# Capstone_Motor_Driver.net
KiCad netlist of a schematic drawn in Altium Designer
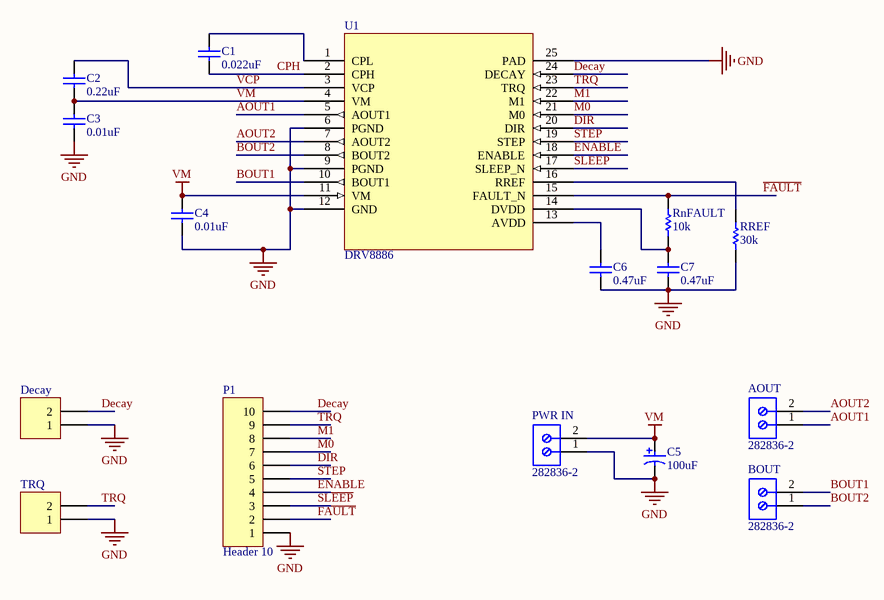
[diagram p0: Capstone_Motor_Driver.SchDoc]

(export (version "E")
  (design (tool "Eeschema 10.0.6"))
  (components
    (comp (ref "AOUT")
      (value "282836-2")
      (footprint "TECO-282836-2_V")
      (description "Female Header, Pitch 5 mm, 1 x 2 Position, Height 10 mm, Tail Length 3.5 mm, Rohs, Bulk")
      (fields (field (name "VOLTAGE") "300V") (field (name "MANUFACTURER") "TE Connectivity"))
      (libsource (lib "IFFF_DRV8886_Power_Breakout") (part "CMP-1684-00017-1"))
    )
    (comp (ref "BOUT")
      (value "282836-2")
      (footprint "TECO-282836-2_V")
      (description "Female Header, Pitch 5 mm, 1 x 2 Position, Height 10 mm, Tail Length 3.5 mm, Rohs, Bulk")
      (fields (field (name "VOLTAGE") "300V") (field (name "MANUFACTURER") "TE Connectivity"))
      (libsource (lib "IFFF_DRV8886_Power_Breakout") (part "CMP-1684-00017-1"))
    )
    (comp (ref "C1")
      (value "0.022uF")
      (footprint "CAPC2013X94X50ML20T25")
      (fields
        (field (name "MANUFACTURER") "AVX Interconnect / Elco")
        (field (name "PART NUMBER") "08055C223JAT2A")
      )
      (libsource (lib "Altium Content Vault") (part "CAP"))
    )
    (comp (ref "C2")
      (value "0.22uF")
      (footprint "CAPC2013X145X50NL20T25")
      (description "0805")
      (fields (field (name "PART NUMBER") "C0805C224K5RAC7800") (field (name "MANUFACTURER") "Kemet"))
      (libsource (lib "Altium Content Vault") (part "CAP"))
    )
    (comp (ref "C3")
      (value "0.01uF")
      (footprint "CAPC2013X88X50ML20T25")
      (description "0805")
      (fields (field (name "MANUFACTURER") "Kemet") (field (name "PART NUMBER") "C0805C103J5RACTU"))
      (libsource (lib "Altium Content Vault") (part "CAP"))
    )
    (comp (ref "C4")
      (value "0.01uF")
      (footprint "CAPC2013X88X50ML20T25")
      (description "0805")
      (fields (field (name "MANUFACTURER") "Kemet") (field (name "PART NUMBER") "C0805C103J5RACTU"))
      (libsource (lib "Altium Content Vault") (part "CAP"))
    )
    (comp (ref "C5")
      (value "100uF")
      (footprint "PNSC-FK-V-F_V")
      (fields (field (name "MANUFACTURER") "Panasonic"))
      (libsource (lib "Altium Content Vault") (part "CAP-P-2"))
    )
    (comp (ref "C6")
      (value "0.47uF")
      (footprint "CAPC2013X110X50NL20T25")
      (description "0805")
      (fields (field (name "MANUFACTURER") "Kemet") (field (name "PART NUMBER") "C0805C474K5RACTU"))
      (libsource (lib "Altium Content Vault") (part "CAP"))
    )
    (comp (ref "C7")
      (value "0.47uF")
      (footprint "CAPC2013X110X50NL20T25")
      (description "0805")
      (fields (field (name "MANUFACTURER") "Kemet") (field (name "PART NUMBER") "C0805C474K5RACTU"))
      (libsource (lib "Altium Content Vault") (part "CAP"))
    )
    (comp (ref "Decay")
      (value "Header 2")
      (footprint "HDR1X2")
      (description "Header, 2-Pin")
      (fields (field (name "PUBLISHER") "Altium Limited"))
      (libsource (lib "Miscellaneous Connectors") (part "Header 2"))
    )
    (comp (ref "P1")
      (value "Header 10")
      (footprint "HDR1X10")
      (description "Header, 10-Pin")
      (fields (field (name "PUBLISHER") "Altium Limited"))
      (libsource (lib "Miscellaneous Connectors") (part "Header 10"))
    )
    (comp (ref "PWR IN")
      (value "282836-2")
      (footprint "TECO-282836-2_V")
      (description "Female Header, Pitch 5 mm, 1 x 2 Position, Height 10 mm, Tail Length 3.5 mm, Rohs, Bulk")
      (fields (field (name "VOLTAGE") "300V") (field (name "MANUFACTURER") "TE Connectivity"))
      (libsource (lib "IFFF_DRV8886_Power_Breakout") (part "CMP-1684-00017-1"))
    )
    (comp (ref "RnFAULT")
      (value "10k")
      (footprint "RESC2013X60X40LL20T25_A")
      (fields (field (name "TOLERANCE") "0.1%") (field (name "MANUFACTURER") "Panasonic"))
      (libsource (lib "Altium Content Vault") (part "RES-2"))
    )
    (comp (ref "RREF")
      (value "30k")
      (footprint "RESC2013X60X40LL20T25_A")
      (fields (field (name "TOLERANCE") "0.1%") (field (name "MANUFACTURER") "Panasonic"))
      (libsource (lib "Altium Content Vault") (part "RES-2"))
    )
    (comp (ref "TRQ")
      (value "Header 2")
      (footprint "HDR1X2")
      (description "Header, 2-Pin")
      (fields (field (name "PUBLISHER") "Altium Limited"))
      (libsource (lib "Miscellaneous Connectors") (part "Header 2"))
    )
    (comp (ref "U1")
      (value "DRV8886")
      (footprint "PWP0024B_N")
      (libsource (lib "IFFF_DRV8886_Power_Breakout") (part "DRV8886"))
    )
  )
  (nets
    (net (code "1") (name "/AOUT1") (class "Default")
      (node (ref "AOUT") (pin "1") (pinfunction "1_1") (pintype "passive"))
      (node (ref "U1") (pin "5") (pinfunction "AOUT1_5") (pintype "output"))
    )
    (net (code "2") (name "/AOUT2") (class "Default")
      (node (ref "AOUT") (pin "2") (pinfunction "2_2") (pintype "passive"))
      (node (ref "U1") (pin "7") (pinfunction "AOUT2_7") (pintype "output"))
    )
    (net (code "3") (name "/BOUT1") (class "Default")
      (node (ref "BOUT") (pin "2") (pinfunction "2_2") (pintype "passive"))
      (node (ref "U1") (pin "10") (pinfunction "BOUT1_10") (pintype "output"))
    )
    (net (code "4") (name "/BOUT2") (class "Default")
      (node (ref "BOUT") (pin "1") (pinfunction "1_1") (pintype "passive"))
      (node (ref "U1") (pin "8") (pinfunction "BOUT2_8") (pintype "output"))
    )
    (net (code "5") (name "/CPH") (class "Default")
      (node (ref "C1") (pin "1") (pinfunction "1_1") (pintype "passive"))
      (node (ref "U1") (pin "2") (pinfunction "CPH_2") (pintype "passive"))
    )
    (net (code "6") (name "/DIR") (class "Default")
      (node (ref "P1") (pin "6") (pinfunction "6_6") (pintype "passive"))
      (node (ref "U1") (pin "20") (pinfunction "DIR_20") (pintype "input"))
    )
    (net (code "7") (name "/Decay") (class "Default")
      (node (ref "Decay") (pin "2") (pinfunction "2_2") (pintype "passive"))
      (node (ref "P1") (pin "10") (pinfunction "10_10") (pintype "passive"))
      (node (ref "U1") (pin "24") (pinfunction "DECAY_24") (pintype "input"))
    )
    (net (code "8") (name "/ENABLE") (class "Default")
      (node (ref "P1") (pin "4") (pinfunction "4_4") (pintype "passive"))
      (node (ref "U1") (pin "18") (pinfunction "ENABLE_18") (pintype "input"))
    )
    (net (code "9") (name "/FAULT") (class "Default")
      (node (ref "P1") (pin "2") (pinfunction "2_2") (pintype "passive"))
      (node (ref "RnFAULT") (pin "2") (pinfunction "2_2") (pintype "passive"))
      (node (ref "U1") (pin "15") (pinfunction "FAULT_N_15") (pintype "passive"))
    )
    (net (code "10") (name "/M0") (class "Default")
      (node (ref "P1") (pin "7") (pinfunction "7_7") (pintype "passive"))
      (node (ref "U1") (pin "21") (pinfunction "M0_21") (pintype "input"))
    )
    (net (code "11") (name "/M1") (class "Default")
      (node (ref "P1") (pin "8") (pinfunction "8_8") (pintype "passive"))
      (node (ref "U1") (pin "22") (pinfunction "M1_22") (pintype "input"))
    )
    (net (code "12") (name "/SLEEP") (class "Default")
      (node (ref "P1") (pin "3") (pinfunction "3_3") (pintype "passive"))
      (node (ref "U1") (pin "17") (pinfunction "SLEEP_N_17") (pintype "input"))
    )
    (net (code "13") (name "/STEP") (class "Default")
      (node (ref "P1") (pin "5") (pinfunction "5_5") (pintype "passive"))
      (node (ref "U1") (pin "19") (pinfunction "STEP_19") (pintype "input"))
    )
    (net (code "14") (name "/TRQ") (class "Default")
      (node (ref "P1") (pin "9") (pinfunction "9_9") (pintype "passive"))
      (node (ref "TRQ") (pin "2") (pinfunction "2_2") (pintype "passive"))
      (node (ref "U1") (pin "23") (pinfunction "TRQ_23") (pintype "input"))
    )
    (net (code "15") (name "/VCP") (class "Default")
      (node (ref "C2") (pin "2") (pinfunction "2_2") (pintype "passive"))
      (node (ref "U1") (pin "3") (pinfunction "VCP_3") (pintype "passive"))
    )
    (net (code "16") (name "GND") (class "Default")
      (node (ref "C3") (pin "1") (pinfunction "1_1") (pintype "passive"))
      (node (ref "C4") (pin "1") (pinfunction "1_1") (pintype "passive"))
      (node (ref "C5") (pin "2") (pinfunction "2_2") (pintype "passive"))
      (node (ref "C6") (pin "1") (pinfunction "1_1") (pintype "passive"))
      (node (ref "C7") (pin "1") (pinfunction "1_1") (pintype "passive"))
      (node (ref "Decay") (pin "1") (pinfunction "1_1") (pintype "passive"))
      (node (ref "P1") (pin "1") (pinfunction "1_1") (pintype "passive"))
      (node (ref "PWR IN") (pin "1") (pinfunction "1_1") (pintype "passive"))
      (node (ref "RREF") (pin "1") (pinfunction "1_1") (pintype "passive"))
      (node (ref "TRQ") (pin "1") (pinfunction "1_1") (pintype "passive"))
      (node (ref "U1") (pin "12") (pinfunction "GND_12") (pintype "passive"))
      (node (ref "U1") (pin "25") (pinfunction "PAD_25") (pintype "passive"))
      (node (ref "U1") (pin "6") (pinfunction "PGND_6") (pintype "passive"))
      (node (ref "U1") (pin "9") (pinfunction "PGND_9") (pintype "passive"))
    )
    (net (code "17") (name "Net-(U1-AVDD)") (class "Default")
      (node (ref "C6") (pin "2") (pinfunction "2_2") (pintype "passive"))
      (node (ref "U1") (pin "13") (pinfunction "AVDD_13") (pintype "passive"))
    )
    (net (code "18") (name "Net-(U1-CPL)") (class "Default")
      (node (ref "C1") (pin "2") (pinfunction "2_2") (pintype "passive"))
      (node (ref "U1") (pin "1") (pinfunction "CPL_1") (pintype "passive"))
    )
    (net (code "19") (name "Net-(U1-DVDD)") (class "Default")
      (node (ref "C7") (pin "2") (pinfunction "2_2") (pintype "passive"))
      (node (ref "RnFAULT") (pin "1") (pinfunction "1_1") (pintype "passive"))
      (node (ref "U1") (pin "14") (pinfunction "DVDD_14") (pintype "passive"))
    )
    (net (code "20") (name "Net-(U1-RREF)") (class "Default")
      (node (ref "RREF") (pin "2") (pinfunction "2_2") (pintype "passive"))
      (node (ref "U1") (pin "16") (pinfunction "RREF_16") (pintype "passive"))
    )
    (net (code "21") (name "VM") (class "Default")
      (node (ref "C2") (pin "1") (pinfunction "1_1") (pintype "passive"))
      (node (ref "C3") (pin "2") (pinfunction "2_2") (pintype "passive"))
      (node (ref "C4") (pin "2") (pinfunction "2_2") (pintype "passive"))
      (node (ref "C5") (pin "1") (pinfunction "1_1") (pintype "passive"))
      (node (ref "PWR IN") (pin "2") (pinfunction "2_2") (pintype "passive"))
      (node (ref "U1") (pin "11") (pinfunction "VM_11") (pintype "input"))
      (node (ref "U1") (pin "4") (pinfunction "VM_4") (pintype "passive"))
    )
  )
)
